# Low_Noise_PS.net
KiCad netlist of a schematic drawn in EAGLE
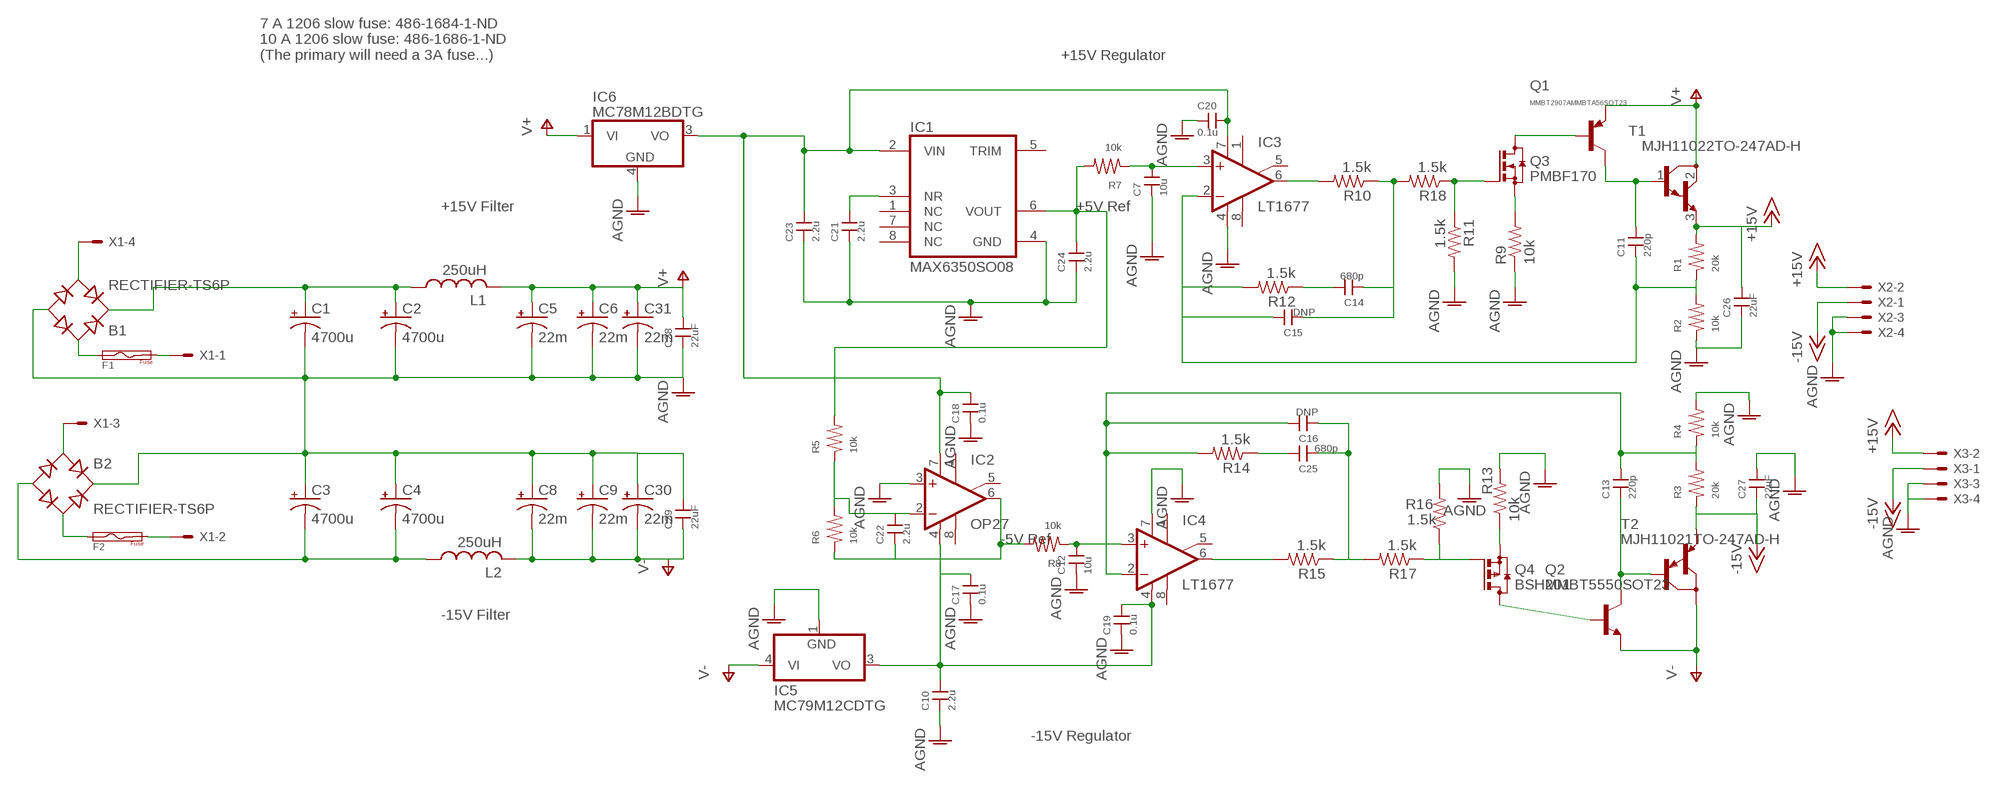
[diagram p0: schematic, sheet 1]

(export (version "E")
  (design (tool "Eeschema 10.0.6"))
  (components
    (comp (ref "B1")
      (value "RECTIFIER-TS6P")
      (footprint "eagle-import:TS6P")
      (libsource (lib "eagle-import") (part "RECTIFIER-TS6P"))
    )
    (comp (ref "B2")
      (value "RECTIFIER-TS6P")
      (footprint "eagle-import:TS6P")
      (libsource (lib "eagle-import") (part "RECTIFIER-TS6P"))
    )
    (comp (ref "C1")
      (value "4700u")
      (footprint "eagle-import:E7,5-18")
      (libsource (lib "eagle-import") (part "CPOL-USE7.5-18"))
    )
    (comp (ref "C2")
      (value "4700u")
      (footprint "eagle-import:E7,5-18")
      (libsource (lib "eagle-import") (part "CPOL-USE7.5-18"))
    )
    (comp (ref "C3")
      (value "4700u")
      (footprint "eagle-import:E7,5-18")
      (libsource (lib "eagle-import") (part "CPOL-USE7.5-18"))
    )
    (comp (ref "C4")
      (value "4700u")
      (footprint "eagle-import:E7,5-18")
      (libsource (lib "eagle-import") (part "CPOL-USE7.5-18"))
    )
    (comp (ref "C5")
      (value "22m")
      (footprint "eagle-import:EB35D")
      (libsource (lib "eagle-import") (part "CPOL-USEB35D"))
    )
    (comp (ref "C6")
      (value "22m")
      (footprint "eagle-import:EB35D")
      (libsource (lib "eagle-import") (part "CPOL-USEB35D"))
    )
    (comp (ref "C7")
      (value "10u")
      (footprint "eagle-import:1206")
      (libsource (lib "eagle-import") (part "CAP1206"))
    )
    (comp (ref "C8")
      (value "22m")
      (footprint "eagle-import:EB35D")
      (libsource (lib "eagle-import") (part "CPOL-USEB35D"))
    )
    (comp (ref "C9")
      (value "22m")
      (footprint "eagle-import:EB35D")
      (libsource (lib "eagle-import") (part "CPOL-USEB35D"))
    )
    (comp (ref "C10")
      (value "2.2u")
      (footprint "eagle-import:1206")
      (libsource (lib "eagle-import") (part "CAP1206"))
    )
    (comp (ref "C11")
      (value "220p")
      (footprint "eagle-import:1206")
      (libsource (lib "eagle-import") (part "CAP1206"))
    )
    (comp (ref "C12")
      (value "10u")
      (footprint "eagle-import:1206")
      (libsource (lib "eagle-import") (part "CAP1206"))
    )
    (comp (ref "C13")
      (value "220p")
      (footprint "eagle-import:1206")
      (libsource (lib "eagle-import") (part "CAP1206"))
    )
    (comp (ref "C14")
      (value "680p")
      (footprint "eagle-import:1206")
      (libsource (lib "eagle-import") (part "CAP1206"))
    )
    (comp (ref "C15")
      (value "DNP")
      (footprint "eagle-import:1206")
      (libsource (lib "eagle-import") (part "CAP1206"))
    )
    (comp (ref "C16")
      (value "DNP")
      (footprint "eagle-import:1206")
      (libsource (lib "eagle-import") (part "CAP1206"))
    )
    (comp (ref "C17")
      (value "0.1u")
      (footprint "eagle-import:1206")
      (libsource (lib "eagle-import") (part "CAP1206"))
    )
    (comp (ref "C18")
      (value "0.1u")
      (footprint "eagle-import:1206")
      (libsource (lib "eagle-import") (part "CAP1206"))
    )
    (comp (ref "C19")
      (value "0.1u")
      (footprint "eagle-import:1206")
      (libsource (lib "eagle-import") (part "CAP1206"))
    )
    (comp (ref "C20")
      (value "0.1u")
      (footprint "eagle-import:1206")
      (libsource (lib "eagle-import") (part "CAP1206"))
    )
    (comp (ref "C21")
      (value "2.2u")
      (footprint "eagle-import:1206")
      (libsource (lib "eagle-import") (part "CAP1206"))
    )
    (comp (ref "C22")
      (value "2.2u")
      (footprint "eagle-import:1206")
      (libsource (lib "eagle-import") (part "CAP1206"))
    )
    (comp (ref "C23")
      (value "2.2u")
      (footprint "eagle-import:1206")
      (libsource (lib "eagle-import") (part "CAP1206"))
    )
    (comp (ref "C24")
      (value "2.2u")
      (footprint "eagle-import:1206")
      (libsource (lib "eagle-import") (part "CAP1206"))
    )
    (comp (ref "C25")
      (value "680p")
      (footprint "eagle-import:1206")
      (libsource (lib "eagle-import") (part "CAP1206"))
    )
    (comp (ref "C26")
      (value "22uF")
      (footprint "eagle-import:1206")
      (libsource (lib "eagle-import") (part "CAP1206"))
    )
    (comp (ref "C27")
      (value "22uF")
      (footprint "eagle-import:1206")
      (libsource (lib "eagle-import") (part "CAP1206"))
    )
    (comp (ref "C28")
      (value "22uF")
      (footprint "eagle-import:1206")
      (libsource (lib "eagle-import") (part "CAP1206"))
    )
    (comp (ref "C29")
      (value "22uF")
      (footprint "eagle-import:1206")
      (libsource (lib "eagle-import") (part "CAP1206"))
    )
    (comp (ref "C30")
      (value "22m")
      (footprint "eagle-import:EB35D")
      (libsource (lib "eagle-import") (part "CPOL-USEB35D"))
    )
    (comp (ref "C31")
      (value "22m")
      (footprint "eagle-import:EB35D")
      (libsource (lib "eagle-import") (part "CPOL-USEB35D"))
    )
    (comp (ref "F1")
      (value "FUSE1206")
      (footprint "eagle-import:FUSE1206")
      (libsource (lib "eagle-import") (part "FUSE1206"))
    )
    (comp (ref "F2")
      (value "FUSE1206")
      (footprint "eagle-import:FUSE1206")
      (libsource (lib "eagle-import") (part "FUSE1206"))
    )
    (comp (ref "IC1")
      (value "MAX6350SO08")
      (footprint "eagle-import:SO08")
      (libsource (lib "eagle-import") (part "MAX6350SO08"))
    )
    (comp (ref "IC2")
      (value "OP27")
      (footprint "eagle-import:SO08")
      (libsource (lib "eagle-import") (part "OPAMP-SO"))
    )
    (comp (ref "IC3")
      (value "LT1677")
      (footprint "eagle-import:SO08")
      (libsource (lib "eagle-import") (part "OPAMP-SO"))
    )
    (comp (ref "IC4")
      (value "LT1677")
      (footprint "eagle-import:SO08")
      (libsource (lib "eagle-import") (part "OPAMP-SO"))
    )
    (comp (ref "IC5")
      (value "MC79M12CDTG")
      (footprint "eagle-import:DPACK_3")
      (libsource (lib "eagle-import") (part "MC79M12CDTG"))
    )
    (comp (ref "IC6")
      (value "MC78M12BDTG")
      (footprint "eagle-import:DPACK_3")
      (libsource (lib "eagle-import") (part "MC78M12BDTG"))
    )
    (comp (ref "L1")
      (value "250uH")
      (footprint "eagle-import:5721-RC")
      (libsource (lib "eagle-import") (part "INDUCTOR5721-RC"))
    )
    (comp (ref "L2")
      (value "250uH")
      (footprint "eagle-import:5721-RC")
      (libsource (lib "eagle-import") (part "INDUCTOR5721-RC"))
    )
    (comp (ref "Q1")
      (value "MMBT2907AMMBTA56SOT23")
      (footprint "eagle-import:SOT23")
      (libsource (lib "eagle-import") (part "MMBT2907ASOT23MMBTA56"))
    )
    (comp (ref "Q2")
      (value "MMBT5550SOT23")
      (footprint "eagle-import:SOT23")
      (libsource (lib "eagle-import") (part "MMBT5550SOT23"))
    )
    (comp (ref "Q3")
      (value "PMBF170")
      (footprint "eagle-import:SOT23")
      (libsource (lib "eagle-import") (part "PMBF170"))
    )
    (comp (ref "Q4")
      (value "BSH201")
      (footprint "eagle-import:SOT23")
      (libsource (lib "eagle-import") (part "BSH201"))
    )
    (comp (ref "R1")
      (value "20k")
      (footprint "eagle-import:1206")
      (libsource (lib "eagle-import") (part "RES1206"))
    )
    (comp (ref "R2")
      (value "10k")
      (footprint "eagle-import:1206")
      (libsource (lib "eagle-import") (part "RES1206"))
    )
    (comp (ref "R3")
      (value "20k")
      (footprint "eagle-import:1206")
      (libsource (lib "eagle-import") (part "RES1206"))
    )
    (comp (ref "R4")
      (value "10k")
      (footprint "eagle-import:1206")
      (libsource (lib "eagle-import") (part "RES1206"))
    )
    (comp (ref "R5")
      (value "10k")
      (footprint "eagle-import:1206")
      (libsource (lib "eagle-import") (part "RES1206"))
    )
    (comp (ref "R6")
      (value "10k")
      (footprint "eagle-import:1206")
      (libsource (lib "eagle-import") (part "RES1206"))
    )
    (comp (ref "R7")
      (value "10k")
      (footprint "eagle-import:1206")
      (libsource (lib "eagle-import") (part "RES1206"))
    )
    (comp (ref "R8")
      (value "10k")
      (footprint "eagle-import:1206")
      (libsource (lib "eagle-import") (part "RES1206"))
    )
    (comp (ref "R9")
      (value "10k")
      (footprint "eagle-import:R1206")
      (libsource (lib "eagle-import") (part "R-US_R1206"))
    )
    (comp (ref "R10")
      (value "1.5k")
      (footprint "eagle-import:R1206")
      (libsource (lib "eagle-import") (part "R-US_R1206"))
    )
    (comp (ref "R11")
      (value "1.5k")
      (footprint "eagle-import:R1206")
      (libsource (lib "eagle-import") (part "R-US_R1206"))
    )
    (comp (ref "R12")
      (value "1.5k")
      (footprint "eagle-import:R1206")
      (libsource (lib "eagle-import") (part "R-US_R1206"))
    )
    (comp (ref "R13")
      (value "10k")
      (footprint "eagle-import:R1206")
      (libsource (lib "eagle-import") (part "R-US_R1206"))
    )
    (comp (ref "R14")
      (value "1.5k")
      (footprint "eagle-import:R1206")
      (libsource (lib "eagle-import") (part "R-US_R1206"))
    )
    (comp (ref "R15")
      (value "1.5k")
      (footprint "eagle-import:R1206")
      (libsource (lib "eagle-import") (part "R-US_R1206"))
    )
    (comp (ref "R16")
      (value "1.5k")
      (footprint "eagle-import:R1206")
      (libsource (lib "eagle-import") (part "R-US_R1206"))
    )
    (comp (ref "R17")
      (value "1.5k")
      (footprint "eagle-import:R1206")
      (libsource (lib "eagle-import") (part "R-US_R1206"))
    )
    (comp (ref "R18")
      (value "1.5k")
      (footprint "eagle-import:R1206")
      (libsource (lib "eagle-import") (part "R-US_R1206"))
    )
    (comp (ref "T1")
      (value "MJH11022TO-247AD-H")
      (footprint "eagle-import:TO-247AD-H")
      (libsource (lib "eagle-import") (part "MJH11022TO-247AD-H"))
    )
    (comp (ref "T2")
      (value "MJH11021TO-247AD-H")
      (footprint "eagle-import:TO-247AD-H")
      (libsource (lib "eagle-import") (part "MJH11021TO-247AD-H"))
    )
    (comp (ref "X1")
      (value "5566-4RA")
      (footprint "eagle-import:5566-4-RA")
      (libsource (lib "eagle-import") (part "5566-4RA"))
    )
    (comp (ref "X2")
      (value "5566-4RA")
      (footprint "eagle-import:5566-4-RA")
      (libsource (lib "eagle-import") (part "5566-4RA"))
    )
    (comp (ref "X3")
      (value "5566-4RA")
      (footprint "eagle-import:5566-4-RA")
      (libsource (lib "eagle-import") (part "5566-4RA"))
    )
  )
  (nets
    (net (code "1") (name "+15V") (class "Default")
      (node (ref "C26") (pin "2") (pinfunction "P$2_2") (pintype "passive"))
      (node (ref "R1") (pin "2") (pinfunction "P$2_2") (pintype "passive"))
      (node (ref "T1") (pin "3") (pinfunction "E_3") (pintype "passive"))
      (node (ref "X2") (pin "2") (pinfunction "S_2") (pintype "passive"))
      (node (ref "X3") (pin "2") (pinfunction "S_2") (pintype "passive"))
    )
    (net (code "2") (name "-15V") (class "Default")
      (node (ref "C27") (pin "1") (pinfunction "P$1_1") (pintype "passive"))
      (node (ref "R3") (pin "1") (pinfunction "P$1_1") (pintype "passive"))
      (node (ref "T2") (pin "3") (pinfunction "E_3") (pintype "passive"))
      (node (ref "X2") (pin "1") (pinfunction "S_1") (pintype "passive"))
      (node (ref "X3") (pin "1") (pinfunction "S_1") (pintype "passive"))
    )
    (net (code "3") (name "AGND") (class "Default")
      (node (ref "B1") (pin "-") (pinfunction "-_-") (pintype "passive"))
      (node (ref "B2") (pin "+") (pinfunction "+_+") (pintype "passive"))
      (node (ref "C1") (pin "-") (pinfunction "-_-") (pintype "passive"))
      (node (ref "C10") (pin "1") (pinfunction "P$1_1") (pintype "passive"))
      (node (ref "C12") (pin "1") (pinfunction "P$1_1") (pintype "passive"))
      (node (ref "C17") (pin "1") (pinfunction "P$1_1") (pintype "passive"))
      (node (ref "C18") (pin "1") (pinfunction "P$1_1") (pintype "passive"))
      (node (ref "C19") (pin "1") (pinfunction "P$1_1") (pintype "passive"))
      (node (ref "C2") (pin "-") (pinfunction "-_-") (pintype "passive"))
      (node (ref "C20") (pin "1") (pinfunction "P$1_1") (pintype "passive"))
      (node (ref "C21") (pin "1") (pinfunction "P$1_1") (pintype "passive"))
      (node (ref "C23") (pin "1") (pinfunction "P$1_1") (pintype "passive"))
      (node (ref "C24") (pin "1") (pinfunction "P$1_1") (pintype "passive"))
      (node (ref "C26") (pin "1") (pinfunction "P$1_1") (pintype "passive"))
      (node (ref "C27") (pin "2") (pinfunction "P$2_2") (pintype "passive"))
      (node (ref "C28") (pin "1") (pinfunction "P$1_1") (pintype "passive"))
      (node (ref "C29") (pin "2") (pinfunction "P$2_2") (pintype "passive"))
      (node (ref "C3") (pin "+") (pinfunction "+_+") (pintype "passive"))
      (node (ref "C30") (pin "+") (pinfunction "+_+") (pintype "passive"))
      (node (ref "C31") (pin "-") (pinfunction "-_-") (pintype "passive"))
      (node (ref "C4") (pin "+") (pinfunction "+_+") (pintype "passive"))
      (node (ref "C5") (pin "-") (pinfunction "-_-") (pintype "passive"))
      (node (ref "C6") (pin "-") (pinfunction "-_-") (pintype "passive"))
      (node (ref "C7") (pin "1") (pinfunction "P$1_1") (pintype "passive"))
      (node (ref "C8") (pin "+") (pinfunction "+_+") (pintype "passive"))
      (node (ref "C9") (pin "+") (pinfunction "+_+") (pintype "passive"))
      (node (ref "IC1") (pin "4") (pinfunction "GND_4") (pintype "power_in"))
      (node (ref "IC2") (pin "3") (pinfunction "+IN_3") (pintype "input"))
      (node (ref "IC3") (pin "4") (pinfunction "V-_4") (pintype "power_in"))
      (node (ref "IC4") (pin "7") (pinfunction "V+_7") (pintype "power_in"))
      (node (ref "IC5") (pin "1") (pinfunction "GND_1") (pintype "passive"))
      (node (ref "IC6") (pin "4") (pinfunction "GND_4") (pintype "passive"))
      (node (ref "R11") (pin "2") (pinfunction "2_2") (pintype "passive"))
      (node (ref "R13") (pin "2") (pinfunction "2_2") (pintype "passive"))
      (node (ref "R16") (pin "2") (pinfunction "2_2") (pintype "passive"))
      (node (ref "R2") (pin "1") (pinfunction "P$1_1") (pintype "passive"))
      (node (ref "R4") (pin "2") (pinfunction "P$2_2") (pintype "passive"))
      (node (ref "R9") (pin "1") (pinfunction "1_1") (pintype "passive"))
      (node (ref "X2") (pin "3") (pinfunction "S_3") (pintype "passive"))
      (node (ref "X2") (pin "4") (pinfunction "S_4") (pintype "passive"))
      (node (ref "X3") (pin "3") (pinfunction "S_3") (pintype "passive"))
      (node (ref "X3") (pin "4") (pinfunction "S_4") (pintype "passive"))
    )
    (net (code "4") (name "Net-(C7-P$2)") (class "Default")
      (node (ref "C7") (pin "2") (pinfunction "P$2_2") (pintype "passive"))
      (node (ref "IC3") (pin "3") (pinfunction "+IN_3") (pintype "input"))
      (node (ref "R7") (pin "1") (pinfunction "P$1_1") (pintype "passive"))
    )
    (net (code "5") (name "Net-(C10-P$2)") (class "Default")
      (node (ref "C10") (pin "2") (pinfunction "P$2_2") (pintype "passive"))
      (node (ref "C17") (pin "2") (pinfunction "P$2_2") (pintype "passive"))
      (node (ref "C19") (pin "2") (pinfunction "P$2_2") (pintype "passive"))
      (node (ref "IC2") (pin "4") (pinfunction "V-_4") (pintype "power_in"))
      (node (ref "IC4") (pin "4") (pinfunction "V-_4") (pintype "power_in"))
      (node (ref "IC5") (pin "3") (pinfunction "VO_3") (pintype "passive"))
    )
    (net (code "6") (name "Net-(C11-P$1)") (class "Default")
      (node (ref "C11") (pin "1") (pinfunction "P$1_1") (pintype "passive"))
      (node (ref "C15") (pin "2") (pinfunction "P$2_2") (pintype "passive"))
      (node (ref "IC3") (pin "2") (pinfunction "-IN_2") (pintype "input"))
      (node (ref "R1") (pin "1") (pinfunction "P$1_1") (pintype "passive"))
      (node (ref "R12") (pin "2") (pinfunction "2_2") (pintype "passive"))
      (node (ref "R2") (pin "2") (pinfunction "P$2_2") (pintype "passive"))
    )
    (net (code "7") (name "Net-(C11-P$2)") (class "Default")
      (node (ref "C11") (pin "2") (pinfunction "P$2_2") (pintype "passive"))
      (node (ref "Q1") (pin "3") (pinfunction "C_3") (pintype "passive"))
      (node (ref "T1") (pin "1") (pinfunction "B_1") (pintype "passive"))
    )
    (net (code "8") (name "Net-(C12-P$2)") (class "Default")
      (node (ref "C12") (pin "2") (pinfunction "P$2_2") (pintype "passive"))
      (node (ref "IC4") (pin "3") (pinfunction "+IN_3") (pintype "input"))
      (node (ref "R8") (pin "1") (pinfunction "P$1_1") (pintype "passive"))
    )
    (net (code "9") (name "Net-(C13-P$1)") (class "Default")
      (node (ref "C13") (pin "1") (pinfunction "P$1_1") (pintype "passive"))
      (node (ref "Q2") (pin "3") (pinfunction "C_3") (pintype "passive"))
      (node (ref "T2") (pin "1") (pinfunction "B_1") (pintype "passive"))
    )
    (net (code "10") (name "Net-(C13-P$2)") (class "Default")
      (node (ref "C13") (pin "2") (pinfunction "P$2_2") (pintype "passive"))
      (node (ref "C16") (pin "2") (pinfunction "P$2_2") (pintype "passive"))
      (node (ref "IC4") (pin "2") (pinfunction "-IN_2") (pintype "input"))
      (node (ref "R14") (pin "2") (pinfunction "2_2") (pintype "passive"))
      (node (ref "R3") (pin "2") (pinfunction "P$2_2") (pintype "passive"))
      (node (ref "R4") (pin "1") (pinfunction "P$1_1") (pintype "passive"))
    )
    (net (code "11") (name "Net-(C14-P$1)") (class "Default")
      (node (ref "C14") (pin "1") (pinfunction "P$1_1") (pintype "passive"))
      (node (ref "C15") (pin "1") (pinfunction "P$1_1") (pintype "passive"))
      (node (ref "R10") (pin "1") (pinfunction "1_1") (pintype "passive"))
      (node (ref "R18") (pin "2") (pinfunction "2_2") (pintype "passive"))
    )
    (net (code "12") (name "Net-(C14-P$2)") (class "Default")
      (node (ref "C14") (pin "2") (pinfunction "P$2_2") (pintype "passive"))
      (node (ref "R12") (pin "1") (pinfunction "1_1") (pintype "passive"))
    )
    (net (code "13") (name "Net-(C16-P$1)") (class "Default")
      (node (ref "C16") (pin "1") (pinfunction "P$1_1") (pintype "passive"))
      (node (ref "C25") (pin "1") (pinfunction "P$1_1") (pintype "passive"))
      (node (ref "R15") (pin "1") (pinfunction "1_1") (pintype "passive"))
      (node (ref "R17") (pin "2") (pinfunction "2_2") (pintype "passive"))
    )
    (net (code "14") (name "Net-(C18-P$2)") (class "Default")
      (node (ref "C18") (pin "2") (pinfunction "P$2_2") (pintype "passive"))
      (node (ref "C20") (pin "2") (pinfunction "P$2_2") (pintype "passive"))
      (node (ref "C23") (pin "2") (pinfunction "P$2_2") (pintype "passive"))
      (node (ref "IC1") (pin "2") (pinfunction "VIN_2") (pintype "input"))
      (node (ref "IC2") (pin "7") (pinfunction "V+_7") (pintype "power_in"))
      (node (ref "IC3") (pin "7") (pinfunction "V+_7") (pintype "power_in"))
      (node (ref "IC6") (pin "3") (pinfunction "VO_3") (pintype "passive"))
    )
    (net (code "15") (name "Net-(C21-P$2)") (class "Default")
      (node (ref "C21") (pin "2") (pinfunction "P$2_2") (pintype "passive"))
      (node (ref "IC1") (pin "3") (pinfunction "NR_3") (pintype "bidirectional"))
    )
    (net (code "16") (name "Net-(C22-P$1)") (class "Default")
      (node (ref "C22") (pin "1") (pinfunction "P$1_1") (pintype "passive"))
      (node (ref "IC2") (pin "6") (pinfunction "OUT_6") (pintype "output"))
      (node (ref "R6") (pin "1") (pinfunction "P$1_1") (pintype "passive"))
      (node (ref "R8") (pin "2") (pinfunction "P$2_2") (pintype "passive"))
    )
    (net (code "17") (name "Net-(C22-P$2)") (class "Default")
      (node (ref "C22") (pin "2") (pinfunction "P$2_2") (pintype "passive"))
      (node (ref "IC2") (pin "2") (pinfunction "-IN_2") (pintype "input"))
      (node (ref "R5") (pin "1") (pinfunction "P$1_1") (pintype "passive"))
      (node (ref "R6") (pin "2") (pinfunction "P$2_2") (pintype "passive"))
    )
    (net (code "18") (name "Net-(C24-P$2)") (class "Default")
      (node (ref "C24") (pin "2") (pinfunction "P$2_2") (pintype "passive"))
      (node (ref "IC1") (pin "6") (pinfunction "VOUT_6") (pintype "power_in"))
      (node (ref "R5") (pin "2") (pinfunction "P$2_2") (pintype "passive"))
      (node (ref "R7") (pin "2") (pinfunction "P$2_2") (pintype "passive"))
    )
    (net (code "19") (name "Net-(C25-P$2)") (class "Default")
      (node (ref "C25") (pin "2") (pinfunction "P$2_2") (pintype "passive"))
      (node (ref "R14") (pin "1") (pinfunction "1_1") (pintype "passive"))
    )
    (net (code "20") (name "Net-(F1-P$1)") (class "Default")
      (node (ref "B1") (pin "AC1") (pinfunction "AC1_AC1") (pintype "passive"))
      (node (ref "F1") (pin "1") (pinfunction "P$1_1") (pintype "bidirectional"))
    )
    (net (code "21") (name "Net-(F1-P$2)") (class "Default")
      (node (ref "F1") (pin "2") (pinfunction "P$2_2") (pintype "bidirectional"))
      (node (ref "X1") (pin "1") (pinfunction "S_1") (pintype "passive"))
    )
    (net (code "22") (name "Net-(F2-P$1)") (class "Default")
      (node (ref "B2") (pin "AC2") (pinfunction "AC2_AC2") (pintype "passive"))
      (node (ref "F2") (pin "1") (pinfunction "P$1_1") (pintype "bidirectional"))
    )
    (net (code "23") (name "Net-(F2-P$2)") (class "Default")
      (node (ref "F2") (pin "2") (pinfunction "P$2_2") (pintype "bidirectional"))
      (node (ref "X1") (pin "2") (pinfunction "S_2") (pintype "passive"))
    )
    (net (code "24") (name "Net-(IC3-OUT)") (class "Default")
      (node (ref "IC3") (pin "6") (pinfunction "OUT_6") (pintype "output"))
      (node (ref "R10") (pin "2") (pinfunction "2_2") (pintype "passive"))
    )
    (net (code "25") (name "Net-(IC4-OUT)") (class "Default")
      (node (ref "IC4") (pin "6") (pinfunction "OUT_6") (pintype "output"))
      (node (ref "R15") (pin "2") (pinfunction "2_2") (pintype "passive"))
    )
    (net (code "26") (name "Net-(L1-1)") (class "Default")
      (node (ref "B1") (pin "+") (pinfunction "+_+") (pintype "passive"))
      (node (ref "C1") (pin "+") (pinfunction "+_+") (pintype "passive"))
      (node (ref "C2") (pin "+") (pinfunction "+_+") (pintype "passive"))
      (node (ref "L1") (pin "P$1") (pinfunction "1_P$1") (pintype "passive"))
    )
    (net (code "27") (name "Net-(L2-1)") (class "Default")
      (node (ref "B2") (pin "-") (pinfunction "-_-") (pintype "passive"))
      (node (ref "C3") (pin "-") (pinfunction "-_-") (pintype "passive"))
      (node (ref "C4") (pin "-") (pinfunction "-_-") (pintype "passive"))
      (node (ref "L2") (pin "P$1") (pinfunction "1_P$1") (pintype "passive"))
    )
    (net (code "28") (name "Net-(Q1-B)") (class "Default")
      (node (ref "Q1") (pin "1") (pinfunction "B_1") (pintype "passive"))
      (node (ref "Q3") (pin "3") (pinfunction "D_3") (pintype "passive"))
    )
    (net (code "29") (name "Net-(Q2-B)") (class "Default")
      (node (ref "Q2") (pin "1") (pinfunction "B_1") (pintype "passive"))
      (node (ref "Q4") (pin "3") (pinfunction "D_3") (pintype "passive"))
    )
    (net (code "30") (name "Net-(Q3-G)") (class "Default")
      (node (ref "Q3") (pin "1") (pinfunction "G_1") (pintype "passive"))
      (node (ref "R11") (pin "1") (pinfunction "1_1") (pintype "passive"))
      (node (ref "R18") (pin "1") (pinfunction "1_1") (pintype "passive"))
    )
    (net (code "31") (name "Net-(Q3-S)") (class "Default")
      (node (ref "Q3") (pin "2") (pinfunction "S_2") (pintype "passive"))
      (node (ref "R9") (pin "2") (pinfunction "2_2") (pintype "passive"))
    )
    (net (code "32") (name "Net-(Q4-G)") (class "Default")
      (node (ref "Q4") (pin "1") (pinfunction "G_1") (pintype "passive"))
      (node (ref "R16") (pin "1") (pinfunction "1_1") (pintype "passive"))
      (node (ref "R17") (pin "1") (pinfunction "1_1") (pintype "passive"))
    )
    (net (code "33") (name "Net-(Q4-S)") (class "Default")
      (node (ref "Q4") (pin "2") (pinfunction "S_2") (pintype "passive"))
      (node (ref "R13") (pin "1") (pinfunction "1_1") (pintype "passive"))
    )
    (net (code "34") (name "Net-(X1C-S)") (class "Default")
      (node (ref "B2") (pin "AC1") (pinfunction "AC1_AC1") (pintype "passive"))
      (node (ref "X1") (pin "3") (pinfunction "S_3") (pintype "passive"))
    )
    (net (code "35") (name "Net-(X1D-S)") (class "Default")
      (node (ref "B1") (pin "AC2") (pinfunction "AC2_AC2") (pintype "passive"))
      (node (ref "X1") (pin "4") (pinfunction "S_4") (pintype "passive"))
    )
    (net (code "36") (name "V+") (class "Default")
      (node (ref "C28") (pin "2") (pinfunction "P$2_2") (pintype "passive"))
      (node (ref "C31") (pin "+") (pinfunction "+_+") (pintype "passive"))
      (node (ref "C5") (pin "+") (pinfunction "+_+") (pintype "passive"))
      (node (ref "C6") (pin "+") (pinfunction "+_+") (pintype "passive"))
      (node (ref "IC6") (pin "1") (pinfunction "VI_1") (pintype "input"))
      (node (ref "L1") (pin "P$2") (pinfunction "2_P$2") (pintype "passive"))
      (node (ref "Q1") (pin "2") (pinfunction "E_2") (pintype "passive"))
      (node (ref "T1") (pin "2") (pinfunction "C_2") (pintype "passive"))
    )
    (net (code "37") (name "V-") (class "Default")
      (node (ref "C29") (pin "1") (pinfunction "P$1_1") (pintype "passive"))
      (node (ref "C30") (pin "-") (pinfunction "-_-") (pintype "passive"))
      (node (ref "C8") (pin "-") (pinfunction "-_-") (pintype "passive"))
      (node (ref "C9") (pin "-") (pinfunction "-_-") (pintype "passive"))
      (node (ref "IC5") (pin "4") (pinfunction "VI_4") (pintype "input"))
      (node (ref "L2") (pin "P$2") (pinfunction "2_P$2") (pintype "passive"))
      (node (ref "Q2") (pin "2") (pinfunction "E_2") (pintype "passive"))
      (node (ref "T2") (pin "2") (pinfunction "C_2") (pintype "passive"))
    )
    (net (code "38") (name "unconnected-(IC1-NC-Pad1)") (class "Default")
      (node (ref "IC1") (pin "1") (pinfunction "NC_1") (pintype "no_connect"))
    )
    (net (code "39") (name "unconnected-(IC1-NC-Pad7)") (class "Default")
      (node (ref "IC1") (pin "7") (pinfunction "NC_7") (pintype "no_connect"))
    )
    (net (code "40") (name "unconnected-(IC1-NC-Pad8)") (class "Default")
      (node (ref "IC1") (pin "8") (pinfunction "NC_8") (pintype "no_connect"))
    )
    (net (code "41") (name "unconnected-(IC1-TRIM-Pad5)") (class "Default")
      (node (ref "IC1") (pin "5") (pinfunction "TRIM_5") (pintype "input"))
    )
    (net (code "42") (name "unconnected-(IC2-ON1-Pad1)") (class "Default")
      (node (ref "IC2") (pin "1") (pinfunction "ON1_1") (pintype "passive"))
    )
    (net (code "43") (name "unconnected-(IC2-ON2-Pad5)") (class "Default")
      (node (ref "IC2") (pin "5") (pinfunction "ON2_5") (pintype "passive"))
    )
    (net (code "44") (name "unconnected-(IC2-OPT-Pad8)") (class "Default")
      (node (ref "IC2") (pin "8") (pinfunction "OPT_8") (pintype "passive"))
    )
    (net (code "45") (name "unconnected-(IC3-ON1-Pad1)") (class "Default")
      (node (ref "IC3") (pin "1") (pinfunction "ON1_1") (pintype "passive"))
    )
    (net (code "46") (name "unconnected-(IC3-ON2-Pad5)") (class "Default")
      (node (ref "IC3") (pin "5") (pinfunction "ON2_5") (pintype "passive"))
    )
    (net (code "47") (name "unconnected-(IC3-OPT-Pad8)") (class "Default")
      (node (ref "IC3") (pin "8") (pinfunction "OPT_8") (pintype "passive"))
    )
    (net (code "48") (name "unconnected-(IC4-ON1-Pad1)") (class "Default")
      (node (ref "IC4") (pin "1") (pinfunction "ON1_1") (pintype "passive"))
    )
    (net (code "49") (name "unconnected-(IC4-ON2-Pad5)") (class "Default")
      (node (ref "IC4") (pin "5") (pinfunction "ON2_5") (pintype "passive"))
    )
    (net (code "50") (name "unconnected-(IC4-OPT-Pad8)") (class "Default")
      (node (ref "IC4") (pin "8") (pinfunction "OPT_8") (pintype "passive"))
    )
  )
)
